# Sheet1.net
KiCad netlist of a schematic drawn in Altium Designer
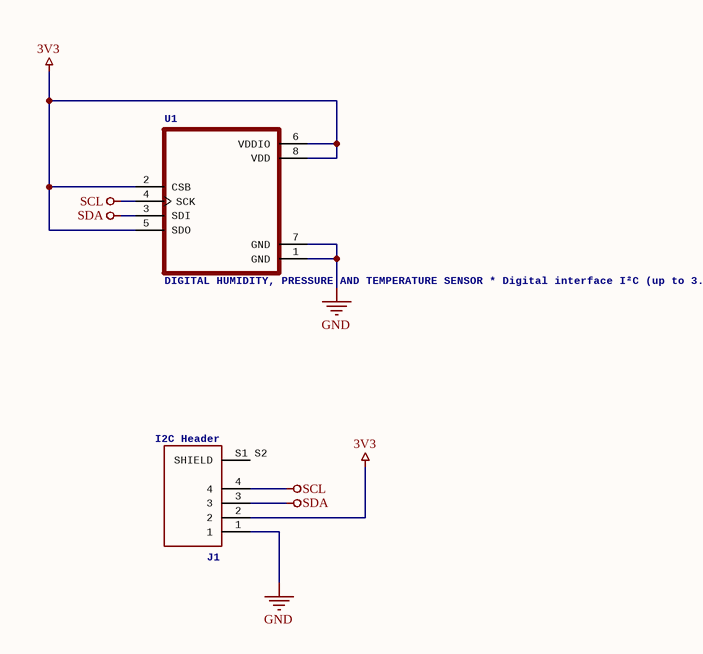
[diagram p0: Sheet1.SchDoc]

(export (version "E")
  (design (tool "Eeschema 10.0.6"))
  (components
    (comp (ref "J1")
      (value "I2C Header")
      (footprint "CONN_BM04B-SRSS-TB(LF)(SN)")
      (fields
        (field (name "MP") "BM04B-SRSS-TB(LF)(SN)")
        (field (name "MF") "JST Sales")
        (field (name "DIGI-KEY_PART_NUMBER") "455-1790-1-ND")
      )
      (libsource (lib "BM04B-SRSS-TB_LF__SN") (part "BM04B-SRSS-TB(LF)(SN)"))
    )
    (comp (ref "U1")
      (value "DIGITAL HUMIDITY, PRESSURE AND TEMPERATURE SENSOR * Digital interface I²C (up to 3.4 MHz) and SPI (3 and 4 wire, up to 10 MHz)* Supply voltage VDD main supply voltage range: 1.71 V to 3.6 V*VDDIO interface voltage range: 1.2 V to 3.6 V Operating range -40…+85 °C, 0…100 % rel. humidity, 300…1100 hPa   The library has been designed by Richard Magdycz Check availability")
      (footprint "PSON65P250X250X100-8N")
      (fields (field (name "MP") "BME280") (field (name "MF") "Bosch"))
      (libsource (lib "BME280") (part "BME280"))
    )
  )
  (nets
    (net (code "1") (name "3V3") (class "Default")
      (node (ref "J1") (pin "2") (pinfunction "2_2") (pintype "passive"))
      (node (ref "U1") (pin "2") (pinfunction "CSB_2") (pintype "passive"))
      (node (ref "U1") (pin "5") (pinfunction "SDO_5") (pintype "passive"))
      (node (ref "U1") (pin "6") (pinfunction "VDDIO_6") (pintype "power_in"))
      (node (ref "U1") (pin "8") (pinfunction "VDD_8") (pintype "power_in"))
    )
    (net (code "2") (name "GND") (class "Default")
      (node (ref "J1") (pin "1") (pinfunction "1_1") (pintype "passive"))
      (node (ref "U1") (pin "1") (pinfunction "GND_1") (pintype "power_in"))
      (node (ref "U1") (pin "7") (pinfunction "GND_7") (pintype "power_in"))
    )
    (net (code "3") (name "SCL") (class "Default")
      (node (ref "J1") (pin "4") (pinfunction "4_4") (pintype "passive"))
      (node (ref "U1") (pin "4") (pinfunction "SCK_4") (pintype "passive"))
    )
    (net (code "4") (name "SDA") (class "Default")
      (node (ref "J1") (pin "3") (pinfunction "3_3") (pintype "passive"))
      (node (ref "U1") (pin "3") (pinfunction "SDI_3") (pintype "passive"))
    )
    (net (code "5") (name "unconnected-(J1-SHIELD-PadS1_S2)") (class "Default")
      (node (ref "J1") (pin "S1_S2") (pinfunction "SHIELD_S1_S2") (pintype "passive"))
    )
  )
)
